# Burn_Wire_Dev_Board.net
KiCad netlist of a schematic drawn in Altium Designer
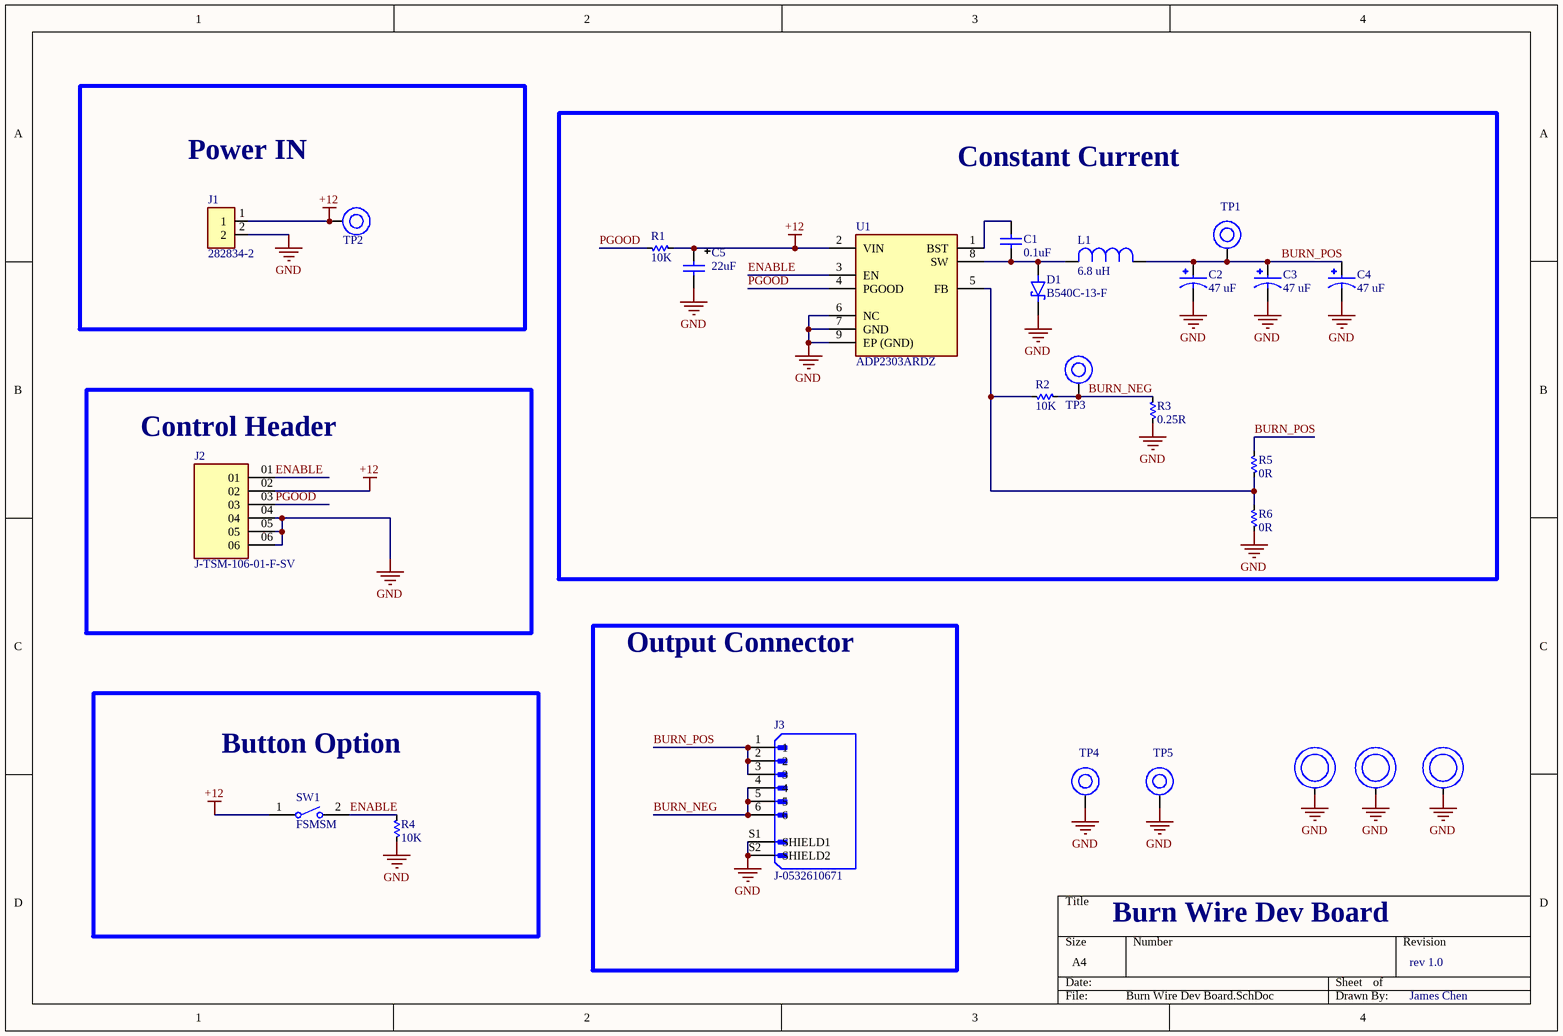
[diagram p0: Burn Wire Dev Board.SchDoc]

(export (version "E")
  (design (tool "Eeschema 10.0.6"))
  (components
    (comp (ref "*1")
      (value "M2 Mounting")
      (footprint "M2 Screws")
      (libsource (lib "RCU Board rev1.0") (part "M2 Mounting"))
    )
    (comp (ref "*2")
      (value "M2 Mounting")
      (footprint "M2 Screws")
      (libsource (lib "RCU Board rev1.0") (part "M2 Mounting"))
    )
    (comp (ref "*3")
      (value "M2 Mounting")
      (footprint "M2 Screws")
      (libsource (lib "RCU Board rev1.0") (part "M2 Mounting"))
    )
    (comp (ref "C1")
      (value "0.1uF")
      (footprint "0603")
      (description "0.1 µF ±10% 25V Ceramic Capacitor X7R 0603 (1608 Metric)")
      (fields
        (field (name "DISTRIBUTOR PART #") "1276-1006-1-ND")
        (field (name "MANUFACTURER") "Samsung Electro-Mechanics")
      )
      (libsource (lib "Burn Wire Dev Board") (part "CC-104-K-25V-X7R-0603"))
    )
    (comp (ref "C2")
      (value "47 uF")
      (footprint "CC-25SVPF47M")
      (description "CAP ALUM POLY 47UF 20% 25V SMD")
      (fields
        (field (name "DISTRIBUTOR PART #") "P16513CT-ND")
        (field (name "MANUFACTURER") "Panasonic Electronic Components")
      )
      (libsource (lib "Burn Wire Dev Board") (part "CC-25SVPF47M"))
    )
    (comp (ref "C3")
      (value "47 uF")
      (footprint "CC-25SVPF47M")
      (description "CAP ALUM POLY 47UF 20% 25V SMD")
      (fields
        (field (name "DISTRIBUTOR PART #") "P16513CT-ND")
        (field (name "MANUFACTURER") "Panasonic Electronic Components")
      )
      (libsource (lib "Burn Wire Dev Board") (part "CC-25SVPF47M"))
    )
    (comp (ref "C4")
      (value "47 uF")
      (footprint "CC-25SVPF47M")
      (description "CAP ALUM POLY 47UF 20% 25V SMD")
      (fields
        (field (name "DISTRIBUTOR PART #") "P16513CT-ND")
        (field (name "MANUFACTURER") "Panasonic Electronic Components")
      )
      (libsource (lib "Burn Wire Dev Board") (part "CC-25SVPF47M"))
    )
    (comp (ref "C5")
      (value "22uF")
      (footprint "CAP TANT 1206 (A) TCJ")
      (description "CAP TANT 22UF 10% 10V 1206")
      (fields
        (field (name "DISTRIBUTOR PART #") "478-11193-1-ND")
        (field (name "MANUFACTURER") "KYOCERA AVX")
      )
      (libsource (lib "Burn Wire Dev Board") (part "CT-225-M-20V-OTH-1206"))
    )
    (comp (ref "D1")
      (value "B540C-13-F")
      (footprint "D-B540C-13-F")
      (description "DIODE SCHOTTKY 40V 5A SMC")
      (fields
        (field (name "MANUFACTURER") "Diodes Incorporated")
        (field (name "DISTRIBUTOR PART #") "B540C-FDICT-ND")
      )
      (libsource (lib "Burn Wire Dev Board") (part "D-B540C-13-F"))
    )
    (comp (ref "J1")
      (value "282834-2")
      (footprint "J-282834-2")
      (description "TERM BLK 2P SIDE ENT 2.54MM PCB")
      (fields
        (field (name "MANUFACTURER") "TE Connectivity AMP Connectors")
        (field (name "DISTRIBUTOR PART #") "A98333-ND")
      )
      (libsource (lib "Burn Wire Dev Board") (part "J-282834-2"))
    )
    (comp (ref "J2")
      (value "J-TSM-106-01-F-SV")
      (footprint "J-TSM-106-01-F-SV")
      (description "CONN HEADER SMD 6POS 2.54MM")
      (fields (field (name "MANUFACTURER") "Samtec Inc.") (field (name "DISTRBUTOR PART #") "SAM12239-ND"))
      (libsource (lib "Burn Wire Dev Board") (part "J-TSM-106-01-F-SV"))
    )
    (comp (ref "J3")
      (value "J-0532610671")
      (footprint "J-0532610671")
      (description "CONN HEADER SMD R/A 6POS 1.25MM")
      (fields
        (field (name "MANFACTURER PART #") "0532610671")
        (field (name "DISTRIBUTOR PART #") "WM7624CT-ND")
      )
      (libsource (lib "Burn Wire Dev Board") (part "J-0532610671"))
    )
    (comp (ref "L1")
      (value "6.8 uH")
      (footprint "L-IHLP4040DZER6R8M01")
      (description "FIXED IND 6.8UH 8A 23.3 MOHM SMD")
      (fields
        (field (name "MANUFACTURER") "Vishay Dale")
        (field (name "MANUFACTURER PART #") "IHLP4040DZER6R8M01")
      )
      (libsource (lib "Burn Wire Dev Board") (part "L-IHLP4040DZER6R8M01"))
    )
    (comp (ref "R1")
      (value "10K")
      (footprint "0603")
      (description "RES 10K OHM 1% 1/8W 0603")
      (fields
        (field (name "DISTRIBUTOR PART #") "RNCP0603FTD10K0CT-ND")
        (field (name "MANUFACTURER") "Stackpole Electronics Inc")
      )
      (libsource (lib "Burn Wire Dev Board") (part "RT-10K0-F-1/16W-0603"))
    )
    (comp (ref "R2")
      (value "10K")
      (footprint "0603")
      (description "RES 10K OHM 1% 1/8W 0603")
      (fields
        (field (name "DISTRIBUTOR PART #") "RNCP0603FTD10K0CT-ND")
        (field (name "MANUFACTURER") "Stackpole Electronics Inc")
      )
      (libsource (lib "Burn Wire Dev Board") (part "RT-10K0-F-1/16W-0603"))
    )
    (comp (ref "R3")
      (value "0.25R")
      (footprint "2010")
      (description "RES 0.25 OHM 1% 3W 2010")
      (fields
        (field (name "DISTRIBUTOR PART #") "541-10112-1-ND")
        (field (name "MANUFACTURER") "Vishay Dale")
      )
      (libsource (lib "Burn Wire Dev Board") (part "RT-0.25R0-F-3W-2010"))
    )
    (comp (ref "R4")
      (value "10K")
      (footprint "0603")
      (description "RES 10K OHM 1% 1/8W 0603")
      (fields
        (field (name "DISTRIBUTOR PART #") "RNCP0603FTD10K0CT-ND")
        (field (name "MANUFACTURER") "Stackpole Electronics Inc")
      )
      (libsource (lib "Burn Wire Dev Board") (part "RT-10K0-F-1/16W-0603"))
    )
    (comp (ref "R5")
      (value "0R")
      (footprint "0603")
      (description "0 Ohms Jumper 0.1W, 1/10W Chip Resistor 0603 (1608 Metric) Automotive AEC-Q200 Thick Film")
      (fields
        (field (name "DISTRIBUTOR PART #") "RMCF0603ZT0R00CT-ND")
        (field (name "MANUFACTURER") "Stackpole Electronics Inc")
      )
      (libsource (lib "Burn Wire Dev Board") (part "RT-0R00-F-1/10W-0603"))
    )
    (comp (ref "R6")
      (value "0R")
      (footprint "0603")
      (description "0 Ohms Jumper 0.1W, 1/10W Chip Resistor 0603 (1608 Metric) Automotive AEC-Q200 Thick Film")
      (fields
        (field (name "DISTRIBUTOR PART #") "RMCF0603ZT0R00CT-ND")
        (field (name "MANUFACTURER") "Stackpole Electronics Inc")
      )
      (libsource (lib "Burn Wire Dev Board") (part "RT-0R00-F-1/10W-0603"))
    )
    (comp (ref "SW1")
      (value "FSMSM")
      (footprint "TECO-FSMSM-2_V")
      (description "FSMSM Push Button Switch, 50 mA, -35 to 85 degC, 2-Pin SMD, RoHS, Bulk")
      (fields (field (name "MANUFACTURER") "TE Connectivity"))
      (libsource (lib "Altium Content Vault") (part "SW-SPST-2_C"))
    )
    (comp (ref "TP1")
      (value "TP")
      (footprint "TP")
      (description "Test Point")
      (libsource (lib "PowerManagmentBoard_V4.0") (part "TP"))
    )
    (comp (ref "TP2")
      (value "TP")
      (footprint "TP")
      (description "Test Point")
      (libsource (lib "PowerManagmentBoard_V4.0") (part "TP"))
    )
    (comp (ref "TP3")
      (value "TP")
      (footprint "TP")
      (description "Test Point")
      (libsource (lib "PowerManagmentBoard_V4.0") (part "TP"))
    )
    (comp (ref "TP4")
      (value "TP")
      (footprint "TP")
      (description "Test Point")
      (libsource (lib "PowerManagmentBoard_V4.0") (part "TP"))
    )
    (comp (ref "TP5")
      (value "TP")
      (footprint "TP")
      (description "Test Point")
      (libsource (lib "PowerManagmentBoard_V4.0") (part "TP"))
    )
    (comp (ref "U1")
      (value "ADP2303ARDZ")
      (footprint "U-ADP2303ARDZ")
      (description "IC REG BUCK ADJUSTABLE 3A 8SOIC")
      (fields
        (field (name "MANUFACTURER") "Analog Devices Inc.")
        (field (name "DISTRIBUTOR PART #") "505-ADP2303ARDZ-ND")
      )
      (libsource (lib "Burn Wire Dev Board") (part "U-ADP2303ARDZ"))
    )
  )
  (nets
    (net (code "1") (name "+12") (class "Default")
      (node (ref "C5") (pin "1") (pinfunction "1_1") (pintype "passive"))
      (node (ref "J1") (pin "1") (pinfunction "1_1") (pintype "passive"))
      (node (ref "J2") (pin "02") (pinfunction "02_02") (pintype "passive"))
      (node (ref "R1") (pin "2") (pintype "passive"))
      (node (ref "SW1") (pin "1") (pinfunction "1_1") (pintype "passive"))
      (node (ref "TP2") (pin "1") (pinfunction "1_1") (pintype "passive"))
      (node (ref "U1") (pin "2") (pinfunction "VIN_2") (pintype "passive"))
    )
    (net (code "2") (name "/BURN_NEG") (class "Default")
      (node (ref "J3") (pin "4") (pinfunction "4_4") (pintype "passive"))
      (node (ref "J3") (pin "5") (pinfunction "5_5") (pintype "passive"))
      (node (ref "J3") (pin "6") (pinfunction "6_6") (pintype "passive"))
      (node (ref "R2") (pin "2") (pintype "passive"))
      (node (ref "R3") (pin "2") (pintype "passive"))
      (node (ref "TP3") (pin "1") (pinfunction "1_1") (pintype "passive"))
    )
    (net (code "3") (name "/BURN_POS") (class "Default")
      (node (ref "C2") (pin "1") (pinfunction "1_1") (pintype "passive"))
      (node (ref "C3") (pin "1") (pinfunction "1_1") (pintype "passive"))
      (node (ref "C4") (pin "1") (pinfunction "1_1") (pintype "passive"))
      (node (ref "J3") (pin "1") (pinfunction "1_1") (pintype "passive"))
      (node (ref "J3") (pin "2") (pinfunction "2_2") (pintype "passive"))
      (node (ref "J3") (pin "3") (pinfunction "3_3") (pintype "passive"))
      (node (ref "L1") (pin "1") (pinfunction "1_1") (pintype "passive"))
      (node (ref "R5") (pin "2") (pintype "passive"))
      (node (ref "TP1") (pin "1") (pinfunction "1_1") (pintype "passive"))
    )
    (net (code "4") (name "/ENABLE") (class "Default")
      (node (ref "J2") (pin "01") (pinfunction "01_01") (pintype "passive"))
      (node (ref "R4") (pin "2") (pintype "passive"))
      (node (ref "SW1") (pin "2") (pinfunction "2_2") (pintype "passive"))
      (node (ref "U1") (pin "3") (pinfunction "EN_3") (pintype "passive"))
    )
    (net (code "5") (name "/PGOOD") (class "Default")
      (node (ref "J2") (pin "03") (pinfunction "03_03") (pintype "passive"))
      (node (ref "R1") (pin "1") (pintype "passive"))
      (node (ref "U1") (pin "4") (pinfunction "PGOOD_4") (pintype "passive"))
    )
    (net (code "6") (name "GND") (class "Default")
      (node (ref "*1") (pin "1") (pintype "passive"))
      (node (ref "*2") (pin "1") (pintype "passive"))
      (node (ref "*3") (pin "1") (pintype "passive"))
      (node (ref "C2") (pin "2") (pinfunction "2_2") (pintype "passive"))
      (node (ref "C3") (pin "2") (pinfunction "2_2") (pintype "passive"))
      (node (ref "C4") (pin "2") (pinfunction "2_2") (pintype "passive"))
      (node (ref "C5") (pin "2") (pinfunction "2_2") (pintype "passive"))
      (node (ref "D1") (pin "C") (pinfunction "K_C") (pintype "passive"))
      (node (ref "J1") (pin "2") (pinfunction "2_2") (pintype "passive"))
      (node (ref "J2") (pin "04") (pinfunction "04_04") (pintype "passive"))
      (node (ref "J2") (pin "05") (pinfunction "05_05") (pintype "passive"))
      (node (ref "J2") (pin "06") (pinfunction "06_06") (pintype "passive"))
      (node (ref "J3") (pin "S1") (pinfunction "SHIELD1_S1") (pintype "passive"))
      (node (ref "J3") (pin "S2") (pinfunction "SHIELD2_S2") (pintype "passive"))
      (node (ref "R3") (pin "1") (pintype "passive"))
      (node (ref "R4") (pin "1") (pintype "passive"))
      (node (ref "R6") (pin "1") (pintype "passive"))
      (node (ref "TP4") (pin "1") (pinfunction "1_1") (pintype "passive"))
      (node (ref "TP5") (pin "1") (pinfunction "1_1") (pintype "passive"))
      (node (ref "U1") (pin "6") (pinfunction "NC_6") (pintype "passive"))
      (node (ref "U1") (pin "7") (pinfunction "GND_7") (pintype "passive"))
      (node (ref "U1") (pin "9") (pinfunction "EP_(GND)_9") (pintype "passive"))
    )
    (net (code "7") (name "Net-(U1-BST)") (class "Default")
      (node (ref "C1") (pin "2") (pinfunction "2_2") (pintype "passive"))
      (node (ref "U1") (pin "1") (pinfunction "BST_1") (pintype "passive"))
    )
    (net (code "8") (name "Net-(U1-FB)") (class "Default")
      (node (ref "R2") (pin "1") (pintype "passive"))
      (node (ref "R5") (pin "1") (pintype "passive"))
      (node (ref "R6") (pin "2") (pintype "passive"))
      (node (ref "U1") (pin "5") (pinfunction "FB_5") (pintype "passive"))
    )
    (net (code "9") (name "Net-(U1-SW)") (class "Default")
      (node (ref "C1") (pin "1") (pinfunction "1_1") (pintype "passive"))
      (node (ref "D1") (pin "A") (pinfunction "A_A") (pintype "passive"))
      (node (ref "L1") (pin "2") (pinfunction "2_2") (pintype "passive"))
      (node (ref "U1") (pin "8") (pinfunction "SW_8") (pintype "passive"))
    )
  )
)
